# Keypad.net
KiCad netlist of a schematic drawn in Altium Designer
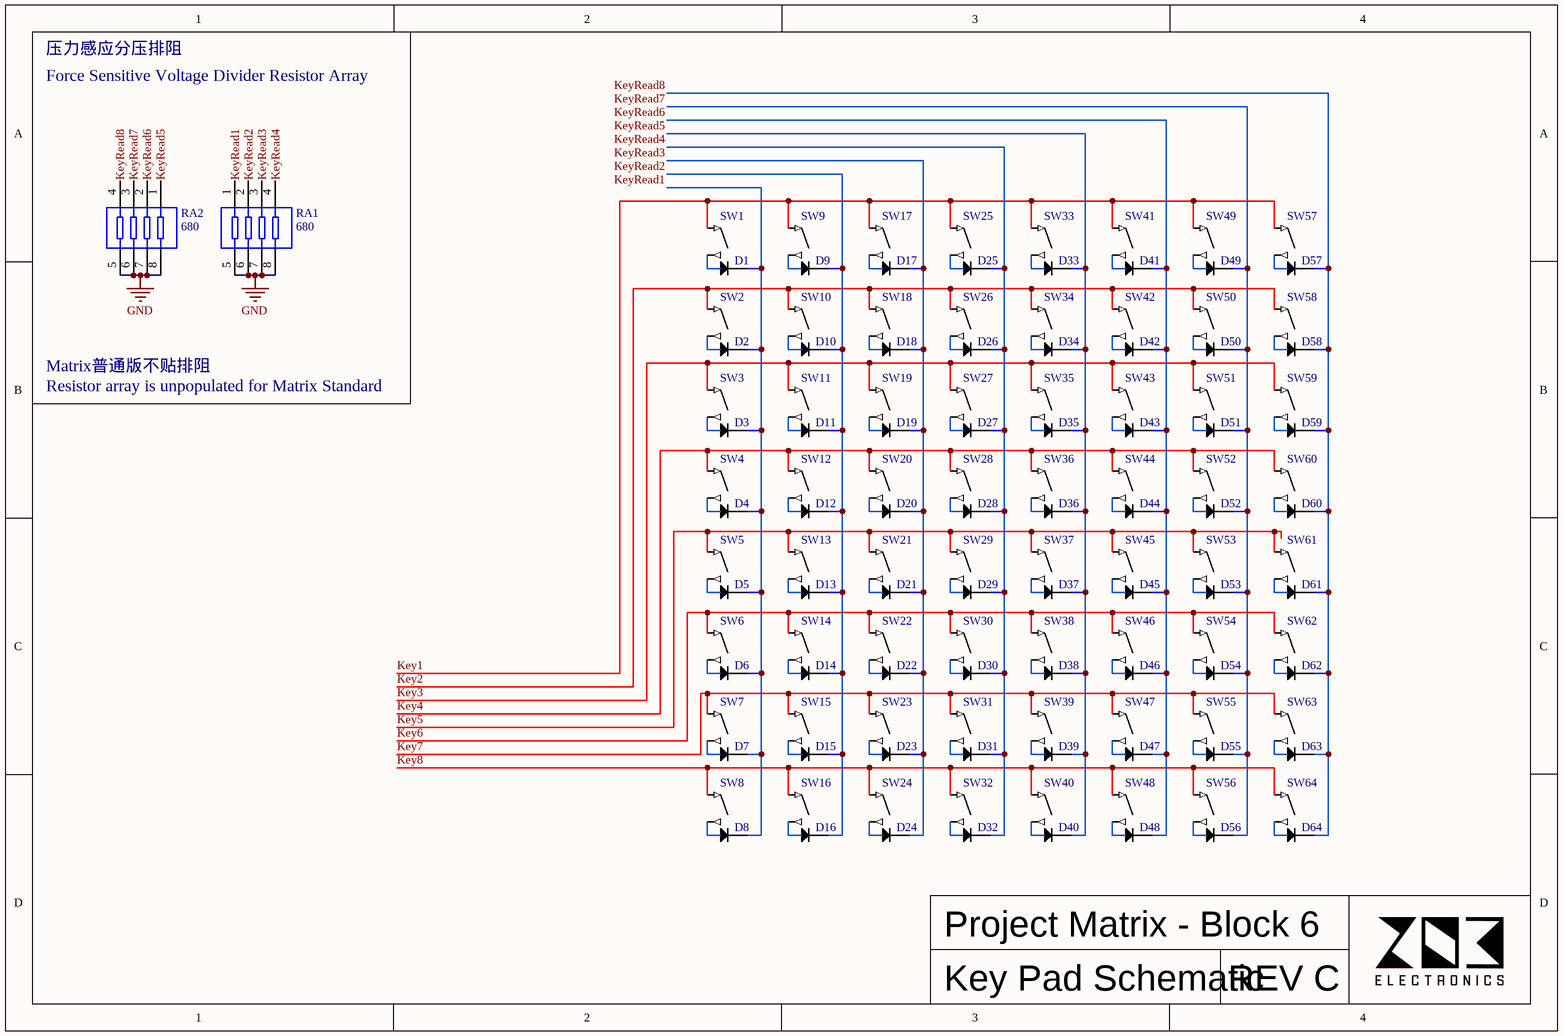
[diagram p0: Keypad.SchDoc]

(export (version "E")
  (design (tool "Eeschema 10.0.6"))
  (components
    (comp (ref "D1") (value "1N4148") (footprint "SOD523") (libsource (lib "Project 64") (part "1N4148")))
    (comp (ref "D2") (value "1N4148") (footprint "SOD523") (libsource (lib "Project 64") (part "1N4148")))
    (comp (ref "D3") (value "1N4148") (footprint "SOD523") (libsource (lib "Project 64") (part "1N4148")))
    (comp (ref "D4") (value "1N4148") (footprint "SOD523") (libsource (lib "Project 64") (part "1N4148")))
    (comp (ref "D5") (value "1N4148") (footprint "SOD523") (libsource (lib "Project 64") (part "1N4148")))
    (comp (ref "D6") (value "1N4148") (footprint "SOD523") (libsource (lib "Project 64") (part "1N4148")))
    (comp (ref "D7") (value "1N4148") (footprint "SOD523") (libsource (lib "Project 64") (part "1N4148")))
    (comp (ref "D8") (value "1N4148") (footprint "SOD523") (libsource (lib "Project 64") (part "1N4148")))
    (comp (ref "D9") (value "1N4148") (footprint "SOD523") (libsource (lib "Project 64") (part "1N4148")))
    (comp (ref "D10") (value "1N4148") (footprint "SOD523") (libsource (lib "Project 64") (part "1N4148")))
    (comp (ref "D11") (value "1N4148") (footprint "SOD523") (libsource (lib "Project 64") (part "1N4148")))
    (comp (ref "D12") (value "1N4148") (footprint "SOD523") (libsource (lib "Project 64") (part "1N4148")))
    (comp (ref "D13") (value "1N4148") (footprint "SOD523") (libsource (lib "Project 64") (part "1N4148")))
    (comp (ref "D14") (value "1N4148") (footprint "SOD523") (libsource (lib "Project 64") (part "1N4148")))
    (comp (ref "D15") (value "1N4148") (footprint "SOD523") (libsource (lib "Project 64") (part "1N4148")))
    (comp (ref "D16") (value "1N4148") (footprint "SOD523") (libsource (lib "Project 64") (part "1N4148")))
    (comp (ref "D17") (value "1N4148") (footprint "SOD523") (libsource (lib "Project 64") (part "1N4148")))
    (comp (ref "D18") (value "1N4148") (footprint "SOD523") (libsource (lib "Project 64") (part "1N4148")))
    (comp (ref "D19") (value "1N4148") (footprint "SOD523") (libsource (lib "Project 64") (part "1N4148")))
    (comp (ref "D20") (value "1N4148") (footprint "SOD523") (libsource (lib "Project 64") (part "1N4148")))
    (comp (ref "D21") (value "1N4148") (footprint "SOD523") (libsource (lib "Project 64") (part "1N4148")))
    (comp (ref "D22") (value "1N4148") (footprint "SOD523") (libsource (lib "Project 64") (part "1N4148")))
    (comp (ref "D23") (value "1N4148") (footprint "SOD523") (libsource (lib "Project 64") (part "1N4148")))
    (comp (ref "D24") (value "1N4148") (footprint "SOD523") (libsource (lib "Project 64") (part "1N4148")))
    (comp (ref "D25") (value "1N4148") (footprint "SOD523") (libsource (lib "Project 64") (part "1N4148")))
    (comp (ref "D26") (value "1N4148") (footprint "SOD523") (libsource (lib "Project 64") (part "1N4148")))
    (comp (ref "D27") (value "1N4148") (footprint "SOD523") (libsource (lib "Project 64") (part "1N4148")))
    (comp (ref "D28") (value "1N4148") (footprint "SOD523") (libsource (lib "Project 64") (part "1N4148")))
    (comp (ref "D29") (value "1N4148") (footprint "SOD523") (libsource (lib "Project 64") (part "1N4148")))
    (comp (ref "D30") (value "1N4148") (footprint "SOD523") (libsource (lib "Project 64") (part "1N4148")))
    (comp (ref "D31") (value "1N4148") (footprint "SOD523") (libsource (lib "Project 64") (part "1N4148")))
    (comp (ref "D32") (value "1N4148") (footprint "SOD523") (libsource (lib "Project 64") (part "1N4148")))
    (comp (ref "D33") (value "1N4148") (footprint "SOD523") (libsource (lib "Project 64") (part "1N4148")))
    (comp (ref "D34") (value "1N4148") (footprint "SOD523") (libsource (lib "Project 64") (part "1N4148")))
    (comp (ref "D35") (value "1N4148") (footprint "SOD523") (libsource (lib "Project 64") (part "1N4148")))
    (comp (ref "D36") (value "1N4148") (footprint "SOD523") (libsource (lib "Project 64") (part "1N4148")))
    (comp (ref "D37") (value "1N4148") (footprint "SOD523") (libsource (lib "Project 64") (part "1N4148")))
    (comp (ref "D38") (value "1N4148") (footprint "SOD523") (libsource (lib "Project 64") (part "1N4148")))
    (comp (ref "D39") (value "1N4148") (footprint "SOD523") (libsource (lib "Project 64") (part "1N4148")))
    (comp (ref "D40") (value "1N4148") (footprint "SOD523") (libsource (lib "Project 64") (part "1N4148")))
    (comp (ref "D41") (value "1N4148") (footprint "SOD523") (libsource (lib "Project 64") (part "1N4148")))
    (comp (ref "D42") (value "1N4148") (footprint "SOD523") (libsource (lib "Project 64") (part "1N4148")))
    (comp (ref "D43") (value "1N4148") (footprint "SOD523") (libsource (lib "Project 64") (part "1N4148")))
    (comp (ref "D44") (value "1N4148") (footprint "SOD523") (libsource (lib "Project 64") (part "1N4148")))
    (comp (ref "D45") (value "1N4148") (footprint "SOD523") (libsource (lib "Project 64") (part "1N4148")))
    (comp (ref "D46") (value "1N4148") (footprint "SOD523") (libsource (lib "Project 64") (part "1N4148")))
    (comp (ref "D47") (value "1N4148") (footprint "SOD523") (libsource (lib "Project 64") (part "1N4148")))
    (comp (ref "D48") (value "1N4148") (footprint "SOD523") (libsource (lib "Project 64") (part "1N4148")))
    (comp (ref "D49") (value "1N4148") (footprint "SOD523") (libsource (lib "Project 64") (part "1N4148")))
    (comp (ref "D50") (value "1N4148") (footprint "SOD523") (libsource (lib "Project 64") (part "1N4148")))
    (comp (ref "D51") (value "1N4148") (footprint "SOD523") (libsource (lib "Project 64") (part "1N4148")))
    (comp (ref "D52") (value "1N4148") (footprint "SOD523") (libsource (lib "Project 64") (part "1N4148")))
    (comp (ref "D53") (value "1N4148") (footprint "SOD523") (libsource (lib "Project 64") (part "1N4148")))
    (comp (ref "D54") (value "1N4148") (footprint "SOD523") (libsource (lib "Project 64") (part "1N4148")))
    (comp (ref "D55") (value "1N4148") (footprint "SOD523") (libsource (lib "Project 64") (part "1N4148")))
    (comp (ref "D56") (value "1N4148") (footprint "SOD523") (libsource (lib "Project 64") (part "1N4148")))
    (comp (ref "D57") (value "1N4148") (footprint "SOD523") (libsource (lib "Project 64") (part "1N4148")))
    (comp (ref "D58") (value "1N4148") (footprint "SOD523") (libsource (lib "Project 64") (part "1N4148")))
    (comp (ref "D59") (value "1N4148") (footprint "SOD523") (libsource (lib "Project 64") (part "1N4148")))
    (comp (ref "D60") (value "1N4148") (footprint "SOD523") (libsource (lib "Project 64") (part "1N4148")))
    (comp (ref "D61") (value "1N4148") (footprint "SOD523") (libsource (lib "Project 64") (part "1N4148")))
    (comp (ref "D62") (value "1N4148") (footprint "SOD523") (libsource (lib "Project 64") (part "1N4148")))
    (comp (ref "D63") (value "1N4148") (footprint "SOD523") (libsource (lib "Project 64") (part "1N4148")))
    (comp (ref "D64") (value "1N4148") (footprint "SOD523") (libsource (lib "Project 64") (part "1N4148")))
    (comp (ref "RA1")
      (value "680")
      (footprint "8P4R")
      (description "Touch Bar")
      (libsource (lib "") (part "4R8P Resistor_1"))
    )
    (comp (ref "RA2")
      (value "680")
      (footprint "8P4R")
      (description "Touch Bar")
      (libsource (lib "203") (part "4R8P Resistor"))
    )
    (comp (ref "SW1") (value "~") (footprint "FSR Pad") (libsource (lib "Project 64") (part "SW")))
    (comp (ref "SW2") (value "~") (footprint "FSR Pad") (libsource (lib "Project 64") (part "SW")))
    (comp (ref "SW3") (value "~") (footprint "FSR Pad") (libsource (lib "Project 64") (part "SW")))
    (comp (ref "SW4") (value "~") (footprint "FSR Pad") (libsource (lib "Project 64") (part "SW")))
    (comp (ref "SW5") (value "~") (footprint "FSR Pad") (libsource (lib "Project 64") (part "SW")))
    (comp (ref "SW6") (value "~") (footprint "FSR Pad") (libsource (lib "Project 64") (part "SW")))
    (comp (ref "SW7") (value "~") (footprint "FSR Pad") (libsource (lib "Project 64") (part "SW")))
    (comp (ref "SW8") (value "~") (footprint "FSR Pad") (libsource (lib "Project 64") (part "SW")))
    (comp (ref "SW9") (value "~") (footprint "FSR Pad") (libsource (lib "Project 64") (part "SW")))
    (comp (ref "SW10") (value "~") (footprint "FSR Pad") (libsource (lib "Project 64") (part "SW")))
    (comp (ref "SW11") (value "~") (footprint "FSR Pad") (libsource (lib "Project 64") (part "SW")))
    (comp (ref "SW12") (value "~") (footprint "FSR Pad") (libsource (lib "Project 64") (part "SW")))
    (comp (ref "SW13") (value "~") (footprint "FSR Pad") (libsource (lib "Project 64") (part "SW")))
    (comp (ref "SW14") (value "~") (footprint "FSR Pad") (libsource (lib "Project 64") (part "SW")))
    (comp (ref "SW15") (value "~") (footprint "FSR Pad") (libsource (lib "Project 64") (part "SW")))
    (comp (ref "SW16") (value "~") (footprint "FSR Pad") (libsource (lib "Project 64") (part "SW")))
    (comp (ref "SW17") (value "~") (footprint "FSR Pad") (libsource (lib "Project 64") (part "SW")))
    (comp (ref "SW18") (value "~") (footprint "FSR Pad") (libsource (lib "Project 64") (part "SW")))
    (comp (ref "SW19") (value "~") (footprint "FSR Pad") (libsource (lib "Project 64") (part "SW")))
    (comp (ref "SW20") (value "~") (footprint "FSR Pad") (libsource (lib "Project 64") (part "SW")))
    (comp (ref "SW21") (value "~") (footprint "FSR Pad") (libsource (lib "Project 64") (part "SW")))
    (comp (ref "SW22") (value "~") (footprint "FSR Pad") (libsource (lib "Project 64") (part "SW")))
    (comp (ref "SW23") (value "~") (footprint "FSR Pad") (libsource (lib "Project 64") (part "SW")))
    (comp (ref "SW24") (value "~") (footprint "FSR Pad") (libsource (lib "Project 64") (part "SW")))
    (comp (ref "SW25") (value "~") (footprint "FSR Pad") (libsource (lib "Project 64") (part "SW")))
    (comp (ref "SW26") (value "~") (footprint "FSR Pad") (libsource (lib "Project 64") (part "SW")))
    (comp (ref "SW27") (value "~") (footprint "FSR Pad") (libsource (lib "Project 64") (part "SW")))
    (comp (ref "SW28") (value "~") (footprint "FSR Pad") (libsource (lib "Project 64") (part "SW")))
    (comp (ref "SW29") (value "~") (footprint "FSR Pad") (libsource (lib "Project 64") (part "SW")))
    (comp (ref "SW30") (value "~") (footprint "FSR Pad") (libsource (lib "Project 64") (part "SW")))
    (comp (ref "SW31") (value "~") (footprint "FSR Pad") (libsource (lib "Project 64") (part "SW")))
    (comp (ref "SW32") (value "~") (footprint "FSR Pad") (libsource (lib "Project 64") (part "SW")))
    (comp (ref "SW33") (value "~") (footprint "FSR Pad") (libsource (lib "Project 64") (part "SW")))
    (comp (ref "SW34") (value "~") (footprint "FSR Pad") (libsource (lib "Project 64") (part "SW")))
    (comp (ref "SW35") (value "~") (footprint "FSR Pad") (libsource (lib "Project 64") (part "SW")))
    (comp (ref "SW36") (value "~") (footprint "FSR Pad") (libsource (lib "Project 64") (part "SW")))
    (comp (ref "SW37") (value "~") (footprint "FSR Pad") (libsource (lib "Project 64") (part "SW")))
    (comp (ref "SW38") (value "~") (footprint "FSR Pad") (libsource (lib "Project 64") (part "SW")))
    (comp (ref "SW39") (value "~") (footprint "FSR Pad") (libsource (lib "Project 64") (part "SW")))
    (comp (ref "SW40") (value "~") (footprint "FSR Pad") (libsource (lib "Project 64") (part "SW")))
    (comp (ref "SW41") (value "~") (footprint "FSR Pad") (libsource (lib "Project 64") (part "SW")))
    (comp (ref "SW42") (value "~") (footprint "FSR Pad") (libsource (lib "Project 64") (part "SW")))
    (comp (ref "SW43") (value "~") (footprint "FSR Pad") (libsource (lib "Project 64") (part "SW")))
    (comp (ref "SW44") (value "~") (footprint "FSR Pad") (libsource (lib "Project 64") (part "SW")))
    (comp (ref "SW45") (value "~") (footprint "FSR Pad") (libsource (lib "Project 64") (part "SW")))
    (comp (ref "SW46") (value "~") (footprint "FSR Pad") (libsource (lib "Project 64") (part "SW")))
    (comp (ref "SW47") (value "~") (footprint "FSR Pad") (libsource (lib "Project 64") (part "SW")))
    (comp (ref "SW48") (value "~") (footprint "FSR Pad") (libsource (lib "Project 64") (part "SW")))
    (comp (ref "SW49") (value "~") (footprint "FSR Pad") (libsource (lib "Project 64") (part "SW")))
    (comp (ref "SW50") (value "~") (footprint "FSR Pad") (libsource (lib "Project 64") (part "SW")))
    (comp (ref "SW51") (value "~") (footprint "FSR Pad") (libsource (lib "Project 64") (part "SW")))
    (comp (ref "SW52") (value "~") (footprint "FSR Pad") (libsource (lib "Project 64") (part "SW")))
    (comp (ref "SW53") (value "~") (footprint "FSR Pad") (libsource (lib "Project 64") (part "SW")))
    (comp (ref "SW54") (value "~") (footprint "FSR Pad") (libsource (lib "Project 64") (part "SW")))
    (comp (ref "SW55") (value "~") (footprint "FSR Pad") (libsource (lib "Project 64") (part "SW")))
    (comp (ref "SW56") (value "~") (footprint "FSR Pad") (libsource (lib "Project 64") (part "SW")))
    (comp (ref "SW57") (value "~") (footprint "FSR Pad") (libsource (lib "Project 64") (part "SW")))
    (comp (ref "SW58") (value "~") (footprint "FSR Pad") (libsource (lib "Project 64") (part "SW")))
    (comp (ref "SW59") (value "~") (footprint "FSR Pad") (libsource (lib "Project 64") (part "SW")))
    (comp (ref "SW60") (value "~") (footprint "FSR Pad") (libsource (lib "Project 64") (part "SW")))
    (comp (ref "SW61") (value "~") (footprint "FSR Pad") (libsource (lib "Project 64") (part "SW")))
    (comp (ref "SW62") (value "~") (footprint "FSR Pad") (libsource (lib "Project 64") (part "SW")))
    (comp (ref "SW63") (value "~") (footprint "FSR Pad") (libsource (lib "Project 64") (part "SW")))
    (comp (ref "SW64") (value "~") (footprint "FSR Pad") (libsource (lib "Project 64") (part "SW")))
  )
  (nets
    (net (code "1") (name "/Key1") (class "Default")
      (node (ref "SW1") (pin "1") (pinfunction "1_1") (pintype "input"))
      (node (ref "SW17") (pin "1") (pinfunction "1_1") (pintype "input"))
      (node (ref "SW25") (pin "1") (pinfunction "1_1") (pintype "input"))
      (node (ref "SW33") (pin "1") (pinfunction "1_1") (pintype "input"))
      (node (ref "SW41") (pin "1") (pinfunction "1_1") (pintype "input"))
      (node (ref "SW49") (pin "1") (pinfunction "1_1") (pintype "input"))
      (node (ref "SW57") (pin "1") (pinfunction "1_1") (pintype "input"))
      (node (ref "SW9") (pin "1") (pinfunction "1_1") (pintype "input"))
    )
    (net (code "2") (name "/Key2") (class "Default")
      (node (ref "SW10") (pin "1") (pinfunction "1_1") (pintype "input"))
      (node (ref "SW18") (pin "1") (pinfunction "1_1") (pintype "input"))
      (node (ref "SW2") (pin "1") (pinfunction "1_1") (pintype "input"))
      (node (ref "SW26") (pin "1") (pinfunction "1_1") (pintype "input"))
      (node (ref "SW34") (pin "1") (pinfunction "1_1") (pintype "input"))
      (node (ref "SW42") (pin "1") (pinfunction "1_1") (pintype "input"))
      (node (ref "SW50") (pin "1") (pinfunction "1_1") (pintype "input"))
      (node (ref "SW58") (pin "1") (pinfunction "1_1") (pintype "input"))
    )
    (net (code "3") (name "/Key3") (class "Default")
      (node (ref "SW11") (pin "1") (pinfunction "1_1") (pintype "input"))
      (node (ref "SW19") (pin "1") (pinfunction "1_1") (pintype "input"))
      (node (ref "SW27") (pin "1") (pinfunction "1_1") (pintype "input"))
      (node (ref "SW3") (pin "1") (pinfunction "1_1") (pintype "input"))
      (node (ref "SW35") (pin "1") (pinfunction "1_1") (pintype "input"))
      (node (ref "SW43") (pin "1") (pinfunction "1_1") (pintype "input"))
      (node (ref "SW51") (pin "1") (pinfunction "1_1") (pintype "input"))
      (node (ref "SW59") (pin "1") (pinfunction "1_1") (pintype "input"))
    )
    (net (code "4") (name "/Key4") (class "Default")
      (node (ref "SW12") (pin "1") (pinfunction "1_1") (pintype "input"))
      (node (ref "SW20") (pin "1") (pinfunction "1_1") (pintype "input"))
      (node (ref "SW28") (pin "1") (pinfunction "1_1") (pintype "input"))
      (node (ref "SW36") (pin "1") (pinfunction "1_1") (pintype "input"))
      (node (ref "SW4") (pin "1") (pinfunction "1_1") (pintype "input"))
      (node (ref "SW44") (pin "1") (pinfunction "1_1") (pintype "input"))
      (node (ref "SW52") (pin "1") (pinfunction "1_1") (pintype "input"))
      (node (ref "SW60") (pin "1") (pinfunction "1_1") (pintype "input"))
    )
    (net (code "5") (name "/Key5") (class "Default")
      (node (ref "SW13") (pin "1") (pinfunction "1_1") (pintype "input"))
      (node (ref "SW21") (pin "1") (pinfunction "1_1") (pintype "input"))
      (node (ref "SW29") (pin "1") (pinfunction "1_1") (pintype "input"))
      (node (ref "SW37") (pin "1") (pinfunction "1_1") (pintype "input"))
      (node (ref "SW45") (pin "1") (pinfunction "1_1") (pintype "input"))
      (node (ref "SW5") (pin "1") (pinfunction "1_1") (pintype "input"))
      (node (ref "SW53") (pin "1") (pinfunction "1_1") (pintype "input"))
      (node (ref "SW61") (pin "1") (pinfunction "1_1") (pintype "input"))
    )
    (net (code "6") (name "/Key6") (class "Default")
      (node (ref "SW14") (pin "1") (pinfunction "1_1") (pintype "input"))
      (node (ref "SW22") (pin "1") (pinfunction "1_1") (pintype "input"))
      (node (ref "SW30") (pin "1") (pinfunction "1_1") (pintype "input"))
      (node (ref "SW38") (pin "1") (pinfunction "1_1") (pintype "input"))
      (node (ref "SW46") (pin "1") (pinfunction "1_1") (pintype "input"))
      (node (ref "SW54") (pin "1") (pinfunction "1_1") (pintype "input"))
      (node (ref "SW6") (pin "1") (pinfunction "1_1") (pintype "input"))
      (node (ref "SW62") (pin "1") (pinfunction "1_1") (pintype "input"))
    )
    (net (code "7") (name "/Key7") (class "Default")
      (node (ref "SW15") (pin "1") (pinfunction "1_1") (pintype "input"))
      (node (ref "SW23") (pin "1") (pinfunction "1_1") (pintype "input"))
      (node (ref "SW31") (pin "1") (pinfunction "1_1") (pintype "input"))
      (node (ref "SW39") (pin "1") (pinfunction "1_1") (pintype "input"))
      (node (ref "SW47") (pin "1") (pinfunction "1_1") (pintype "input"))
      (node (ref "SW55") (pin "1") (pinfunction "1_1") (pintype "input"))
      (node (ref "SW63") (pin "1") (pinfunction "1_1") (pintype "input"))
      (node (ref "SW7") (pin "1") (pinfunction "1_1") (pintype "input"))
    )
    (net (code "8") (name "/Key8") (class "Default")
      (node (ref "SW16") (pin "1") (pinfunction "1_1") (pintype "input"))
      (node (ref "SW24") (pin "1") (pinfunction "1_1") (pintype "input"))
      (node (ref "SW32") (pin "1") (pinfunction "1_1") (pintype "input"))
      (node (ref "SW40") (pin "1") (pinfunction "1_1") (pintype "input"))
      (node (ref "SW48") (pin "1") (pinfunction "1_1") (pintype "input"))
      (node (ref "SW56") (pin "1") (pinfunction "1_1") (pintype "input"))
      (node (ref "SW64") (pin "1") (pinfunction "1_1") (pintype "input"))
      (node (ref "SW8") (pin "1") (pinfunction "1_1") (pintype "input"))
    )
    (net (code "9") (name "/KeyRead1") (class "Default")
      (node (ref "D1") (pin "2") (pinfunction "2_2") (pintype "passive"))
      (node (ref "D2") (pin "2") (pinfunction "2_2") (pintype "passive"))
      (node (ref "D3") (pin "2") (pinfunction "2_2") (pintype "passive"))
      (node (ref "D4") (pin "2") (pinfunction "2_2") (pintype "passive"))
      (node (ref "D5") (pin "2") (pinfunction "2_2") (pintype "passive"))
      (node (ref "D6") (pin "2") (pinfunction "2_2") (pintype "passive"))
      (node (ref "D7") (pin "2") (pinfunction "2_2") (pintype "passive"))
      (node (ref "D8") (pin "2") (pinfunction "2_2") (pintype "passive"))
      (node (ref "RA1") (pin "1") (pinfunction "1_1") (pintype "passive"))
    )
    (net (code "10") (name "/KeyRead2") (class "Default")
      (node (ref "D10") (pin "2") (pinfunction "2_2") (pintype "passive"))
      (node (ref "D11") (pin "2") (pinfunction "2_2") (pintype "passive"))
      (node (ref "D12") (pin "2") (pinfunction "2_2") (pintype "passive"))
      (node (ref "D13") (pin "2") (pinfunction "2_2") (pintype "passive"))
      (node (ref "D14") (pin "2") (pinfunction "2_2") (pintype "passive"))
      (node (ref "D15") (pin "2") (pinfunction "2_2") (pintype "passive"))
      (node (ref "D16") (pin "2") (pinfunction "2_2") (pintype "passive"))
      (node (ref "D9") (pin "2") (pinfunction "2_2") (pintype "passive"))
      (node (ref "RA1") (pin "2") (pinfunction "2_2") (pintype "passive"))
    )
    (net (code "11") (name "/KeyRead3") (class "Default")
      (node (ref "D17") (pin "2") (pinfunction "2_2") (pintype "passive"))
      (node (ref "D18") (pin "2") (pinfunction "2_2") (pintype "passive"))
      (node (ref "D19") (pin "2") (pinfunction "2_2") (pintype "passive"))
      (node (ref "D20") (pin "2") (pinfunction "2_2") (pintype "passive"))
      (node (ref "D21") (pin "2") (pinfunction "2_2") (pintype "passive"))
      (node (ref "D22") (pin "2") (pinfunction "2_2") (pintype "passive"))
      (node (ref "D23") (pin "2") (pinfunction "2_2") (pintype "passive"))
      (node (ref "D24") (pin "2") (pinfunction "2_2") (pintype "passive"))
      (node (ref "RA1") (pin "3") (pinfunction "3_3") (pintype "passive"))
    )
    (net (code "12") (name "/KeyRead4") (class "Default")
      (node (ref "D25") (pin "2") (pinfunction "2_2") (pintype "passive"))
      (node (ref "D26") (pin "2") (pinfunction "2_2") (pintype "passive"))
      (node (ref "D27") (pin "2") (pinfunction "2_2") (pintype "passive"))
      (node (ref "D28") (pin "2") (pinfunction "2_2") (pintype "passive"))
      (node (ref "D29") (pin "2") (pinfunction "2_2") (pintype "passive"))
      (node (ref "D30") (pin "2") (pinfunction "2_2") (pintype "passive"))
      (node (ref "D31") (pin "2") (pinfunction "2_2") (pintype "passive"))
      (node (ref "D32") (pin "2") (pinfunction "2_2") (pintype "passive"))
      (node (ref "RA1") (pin "4") (pinfunction "4_4") (pintype "passive"))
    )
    (net (code "13") (name "/KeyRead5") (class "Default")
      (node (ref "D33") (pin "2") (pinfunction "2_2") (pintype "passive"))
      (node (ref "D34") (pin "2") (pinfunction "2_2") (pintype "passive"))
      (node (ref "D35") (pin "2") (pinfunction "2_2") (pintype "passive"))
      (node (ref "D36") (pin "2") (pinfunction "2_2") (pintype "passive"))
      (node (ref "D37") (pin "2") (pinfunction "2_2") (pintype "passive"))
      (node (ref "D38") (pin "2") (pinfunction "2_2") (pintype "passive"))
      (node (ref "D39") (pin "2") (pinfunction "2_2") (pintype "passive"))
      (node (ref "D40") (pin "2") (pinfunction "2_2") (pintype "passive"))
      (node (ref "RA2") (pin "1") (pinfunction "1_1") (pintype "passive"))
    )
    (net (code "14") (name "/KeyRead6") (class "Default")
      (node (ref "D41") (pin "2") (pinfunction "2_2") (pintype "passive"))
      (node (ref "D42") (pin "2") (pinfunction "2_2") (pintype "passive"))
      (node (ref "D43") (pin "2") (pinfunction "2_2") (pintype "passive"))
      (node (ref "D44") (pin "2") (pinfunction "2_2") (pintype "passive"))
      (node (ref "D45") (pin "2") (pinfunction "2_2") (pintype "passive"))
      (node (ref "D46") (pin "2") (pinfunction "2_2") (pintype "passive"))
      (node (ref "D47") (pin "2") (pinfunction "2_2") (pintype "passive"))
      (node (ref "D48") (pin "2") (pinfunction "2_2") (pintype "passive"))
      (node (ref "RA2") (pin "2") (pinfunction "2_2") (pintype "passive"))
    )
    (net (code "15") (name "/KeyRead7") (class "Default")
      (node (ref "D49") (pin "2") (pinfunction "2_2") (pintype "passive"))
      (node (ref "D50") (pin "2") (pinfunction "2_2") (pintype "passive"))
      (node (ref "D51") (pin "2") (pinfunction "2_2") (pintype "passive"))
      (node (ref "D52") (pin "2") (pinfunction "2_2") (pintype "passive"))
      (node (ref "D53") (pin "2") (pinfunction "2_2") (pintype "passive"))
      (node (ref "D54") (pin "2") (pinfunction "2_2") (pintype "passive"))
      (node (ref "D55") (pin "2") (pinfunction "2_2") (pintype "passive"))
      (node (ref "D56") (pin "2") (pinfunction "2_2") (pintype "passive"))
      (node (ref "RA2") (pin "3") (pinfunction "3_3") (pintype "passive"))
    )
    (net (code "16") (name "/KeyRead8") (class "Default")
      (node (ref "D57") (pin "2") (pinfunction "2_2") (pintype "passive"))
      (node (ref "D58") (pin "2") (pinfunction "2_2") (pintype "passive"))
      (node (ref "D59") (pin "2") (pinfunction "2_2") (pintype "passive"))
      (node (ref "D60") (pin "2") (pinfunction "2_2") (pintype "passive"))
      (node (ref "D61") (pin "2") (pinfunction "2_2") (pintype "passive"))
      (node (ref "D62") (pin "2") (pinfunction "2_2") (pintype "passive"))
      (node (ref "D63") (pin "2") (pinfunction "2_2") (pintype "passive"))
      (node (ref "D64") (pin "2") (pinfunction "2_2") (pintype "passive"))
      (node (ref "RA2") (pin "4") (pinfunction "4_4") (pintype "passive"))
    )
    (net (code "17") (name "GND") (class "Default")
      (node (ref "RA1") (pin "5") (pinfunction "5_5") (pintype "passive"))
      (node (ref "RA1") (pin "6") (pinfunction "6_6") (pintype "passive"))
      (node (ref "RA1") (pin "7") (pinfunction "7_7") (pintype "passive"))
      (node (ref "RA1") (pin "8") (pinfunction "8_8") (pintype "passive"))
      (node (ref "RA2") (pin "5") (pinfunction "5_5") (pintype "passive"))
      (node (ref "RA2") (pin "6") (pinfunction "6_6") (pintype "passive"))
      (node (ref "RA2") (pin "7") (pinfunction "7_7") (pintype "passive"))
      (node (ref "RA2") (pin "8") (pinfunction "8_8") (pintype "passive"))
    )
    (net (code "18") (name "Net-(SW1-Out)") (class "Default")
      (node (ref "D1") (pin "1") (pinfunction "1_1") (pintype "passive"))
      (node (ref "SW1") (pin "2") (pinfunction "Out_2") (pintype "output"))
    )
    (net (code "19") (name "Net-(SW2-Out)") (class "Default")
      (node (ref "D2") (pin "1") (pinfunction "1_1") (pintype "passive"))
      (node (ref "SW2") (pin "2") (pinfunction "Out_2") (pintype "output"))
    )
    (net (code "20") (name "Net-(SW3-Out)") (class "Default")
      (node (ref "D3") (pin "1") (pinfunction "1_1") (pintype "passive"))
      (node (ref "SW3") (pin "2") (pinfunction "Out_2") (pintype "output"))
    )
    (net (code "21") (name "Net-(SW4-Out)") (class "Default")
      (node (ref "D4") (pin "1") (pinfunction "1_1") (pintype "passive"))
      (node (ref "SW4") (pin "2") (pinfunction "Out_2") (pintype "output"))
    )
    (net (code "22") (name "Net-(SW5-Out)") (class "Default")
      (node (ref "D5") (pin "1") (pinfunction "1_1") (pintype "passive"))
      (node (ref "SW5") (pin "2") (pinfunction "Out_2") (pintype "output"))
    )
    (net (code "23") (name "Net-(SW6-Out)") (class "Default")
      (node (ref "D6") (pin "1") (pinfunction "1_1") (pintype "passive"))
      (node (ref "SW6") (pin "2") (pinfunction "Out_2") (pintype "output"))
    )
    (net (code "24") (name "Net-(SW7-Out)") (class "Default")
      (node (ref "D7") (pin "1") (pinfunction "1_1") (pintype "passive"))
      (node (ref "SW7") (pin "2") (pinfunction "Out_2") (pintype "output"))
    )
    (net (code "25") (name "Net-(SW8-Out)") (class "Default")
      (node (ref "D8") (pin "1") (pinfunction "1_1") (pintype "passive"))
      (node (ref "SW8") (pin "2") (pinfunction "Out_2") (pintype "output"))
    )
    (net (code "26") (name "Net-(SW9-Out)") (class "Default")
      (node (ref "D9") (pin "1") (pinfunction "1_1") (pintype "passive"))
      (node (ref "SW9") (pin "2") (pinfunction "Out_2") (pintype "output"))
    )
    (net (code "27") (name "Net-(SW10-Out)") (class "Default")
      (node (ref "D10") (pin "1") (pinfunction "1_1") (pintype "passive"))
      (node (ref "SW10") (pin "2") (pinfunction "Out_2") (pintype "output"))
    )
    (net (code "28") (name "Net-(SW11-Out)") (class "Default")
      (node (ref "D11") (pin "1") (pinfunction "1_1") (pintype "passive"))
      (node (ref "SW11") (pin "2") (pinfunction "Out_2") (pintype "output"))
    )
    (net (code "29") (name "Net-(SW12-Out)") (class "Default")
      (node (ref "D12") (pin "1") (pinfunction "1_1") (pintype "passive"))
      (node (ref "SW12") (pin "2") (pinfunction "Out_2") (pintype "output"))
    )
    (net (code "30") (name "Net-(SW13-Out)") (class "Default")
      (node (ref "D13") (pin "1") (pinfunction "1_1") (pintype "passive"))
      (node (ref "SW13") (pin "2") (pinfunction "Out_2") (pintype "output"))
    )
    (net (code "31") (name "Net-(SW14-Out)") (class "Default")
      (node (ref "D14") (pin "1") (pinfunction "1_1") (pintype "passive"))
      (node (ref "SW14") (pin "2") (pinfunction "Out_2") (pintype "output"))
    )
    (net (code "32") (name "Net-(SW15-Out)") (class "Default")
      (node (ref "D15") (pin "1") (pinfunction "1_1") (pintype "passive"))
      (node (ref "SW15") (pin "2") (pinfunction "Out_2") (pintype "output"))
    )
    (net (code "33") (name "Net-(SW16-Out)") (class "Default")
      (node (ref "D16") (pin "1") (pinfunction "1_1") (pintype "passive"))
      (node (ref "SW16") (pin "2") (pinfunction "Out_2") (pintype "output"))
    )
    (net (code "34") (name "Net-(SW17-Out)") (class "Default")
      (node (ref "D17") (pin "1") (pinfunction "1_1") (pintype "passive"))
      (node (ref "SW17") (pin "2") (pinfunction "Out_2") (pintype "output"))
    )
    (net (code "35") (name "Net-(SW18-Out)") (class "Default")
      (node (ref "D18") (pin "1") (pinfunction "1_1") (pintype "passive"))
      (node (ref "SW18") (pin "2") (pinfunction "Out_2") (pintype "output"))
    )
    (net (code "36") (name "Net-(SW19-Out)") (class "Default")
      (node (ref "D19") (pin "1") (pinfunction "1_1") (pintype "passive"))
      (node (ref "SW19") (pin "2") (pinfunction "Out_2") (pintype "output"))
    )
    (net (code "37") (name "Net-(SW20-Out)") (class "Default")
      (node (ref "D20") (pin "1") (pinfunction "1_1") (pintype "passive"))
      (node (ref "SW20") (pin "2") (pinfunction "Out_2") (pintype "output"))
    )
    (net (code "38") (name "Net-(SW21-Out)") (class "Default")
      (node (ref "D21") (pin "1") (pinfunction "1_1") (pintype "passive"))
      (node (ref "SW21") (pin "2") (pinfunction "Out_2") (pintype "output"))
    )
    (net (code "39") (name "Net-(SW22-Out)") (class "Default")
      (node (ref "D22") (pin "1") (pinfunction "1_1") (pintype "passive"))
      (node (ref "SW22") (pin "2") (pinfunction "Out_2") (pintype "output"))
    )
    (net (code "40") (name "Net-(SW23-Out)") (class "Default")
      (node (ref "D23") (pin "1") (pinfunction "1_1") (pintype "passive"))
      (node (ref "SW23") (pin "2") (pinfunction "Out_2") (pintype "output"))
    )
    (net (code "41") (name "Net-(SW24-Out)") (class "Default")
      (node (ref "D24") (pin "1") (pinfunction "1_1") (pintype "passive"))
      (node (ref "SW24") (pin "2") (pinfunction "Out_2") (pintype "output"))
    )
    (net (code "42") (name "Net-(SW25-Out)") (class "Default")
      (node (ref "D25") (pin "1") (pinfunction "1_1") (pintype "passive"))
      (node (ref "SW25") (pin "2") (pinfunction "Out_2") (pintype "output"))
    )
    (net (code "43") (name "Net-(SW26-Out)") (class "Default")
      (node (ref "D26") (pin "1") (pinfunction "1_1") (pintype "passive"))
      (node (ref "SW26") (pin "2") (pinfunction "Out_2") (pintype "output"))
    )
    (net (code "44") (name "Net-(SW27-Out)") (class "Default")
      (node (ref "D27") (pin "1") (pinfunction "1_1") (pintype "passive"))
      (node (ref "SW27") (pin "2") (pinfunction "Out_2") (pintype "output"))
    )
    (net (code "45") (name "Net-(SW28-Out)") (class "Default")
      (node (ref "D28") (pin "1") (pinfunction "1_1") (pintype "passive"))
      (node (ref "SW28") (pin "2") (pinfunction "Out_2") (pintype "output"))
    )
    (net (code "46") (name "Net-(SW29-Out)") (class "Default")
      (node (ref "D29") (pin "1") (pinfunction "1_1") (pintype "passive"))
      (node (ref "SW29") (pin "2") (pinfunction "Out_2") (pintype "output"))
    )
    (net (code "47") (name "Net-(SW30-Out)") (class "Default")
      (node (ref "D30") (pin "1") (pinfunction "1_1") (pintype "passive"))
      (node (ref "SW30") (pin "2") (pinfunction "Out_2") (pintype "output"))
    )
    (net (code "48") (name "Net-(SW31-Out)") (class "Default")
      (node (ref "D31") (pin "1") (pinfunction "1_1") (pintype "passive"))
      (node (ref "SW31") (pin "2") (pinfunction "Out_2") (pintype "output"))
    )
    (net (code "49") (name "Net-(SW32-Out)") (class "Default")
      (node (ref "D32") (pin "1") (pinfunction "1_1") (pintype "passive"))
      (node (ref "SW32") (pin "2") (pinfunction "Out_2") (pintype "output"))
    )
    (net (code "50") (name "Net-(SW33-Out)") (class "Default")
      (node (ref "D33") (pin "1") (pinfunction "1_1") (pintype "passive"))
      (node (ref "SW33") (pin "2") (pinfunction "Out_2") (pintype "output"))
    )
    (net (code "51") (name "Net-(SW34-Out)") (class "Default")
      (node (ref "D34") (pin "1") (pinfunction "1_1") (pintype "passive"))
      (node (ref "SW34") (pin "2") (pinfunction "Out_2") (pintype "output"))
    )
    (net (code "52") (name "Net-(SW35-Out)") (class "Default")
      (node (ref "D35") (pin "1") (pinfunction "1_1") (pintype "passive"))
      (node (ref "SW35") (pin "2") (pinfunction "Out_2") (pintype "output"))
    )
    (net (code "53") (name "Net-(SW36-Out)") (class "Default")
      (node (ref "D36") (pin "1") (pinfunction "1_1") (pintype "passive"))
      (node (ref "SW36") (pin "2") (pinfunction "Out_2") (pintype "output"))
    )
    (net (code "54") (name "Net-(SW37-Out)") (class "Default")
      (node (ref "D37") (pin "1") (pinfunction "1_1") (pintype "passive"))
      (node (ref "SW37") (pin "2") (pinfunction "Out_2") (pintype "output"))
    )
    (net (code "55") (name "Net-(SW38-Out)") (class "Default")
      (node (ref "D38") (pin "1") (pinfunction "1_1") (pintype "passive"))
      (node (ref "SW38") (pin "2") (pinfunction "Out_2") (pintype "output"))
    )
    (net (code "56") (name "Net-(SW39-Out)") (class "Default")
      (node (ref "D39") (pin "1") (pinfunction "1_1") (pintype "passive"))
      (node (ref "SW39") (pin "2") (pinfunction "Out_2") (pintype "output"))
    )
    (net (code "57") (name "Net-(SW40-Out)") (class "Default")
      (node (ref "D40") (pin "1") (pinfunction "1_1") (pintype "passive"))
      (node (ref "SW40") (pin "2") (pinfunction "Out_2") (pintype "output"))
    )
    (net (code "58") (name "Net-(SW41-Out)") (class "Default")
      (node (ref "D41") (pin "1") (pinfunction "1_1") (pintype "passive"))
      (node (ref "SW41") (pin "2") (pinfunction "Out_2") (pintype "output"))
    )
    (net (code "59") (name "Net-(SW42-Out)") (class "Default")
      (node (ref "D42") (pin "1") (pinfunction "1_1") (pintype "passive"))
      (node (ref "SW42") (pin "2") (pinfunction "Out_2") (pintype "output"))
    )
    (net (code "60") (name "Net-(SW43-Out)") (class "Default")
      (node (ref "D43") (pin "1") (pinfunction "1_1") (pintype "passive"))
      (node (ref "SW43") (pin "2") (pinfunction "Out_2") (pintype "output"))
    )
    (net (code "61") (name "Net-(SW44-Out)") (class "Default")
      (node (ref "D44") (pin "1") (pinfunction "1_1") (pintype "passive"))
      (node (ref "SW44") (pin "2") (pinfunction "Out_2") (pintype "output"))
    )
    (net (code "62") (name "Net-(SW45-Out)") (class "Default")
      (node (ref "D45") (pin "1") (pinfunction "1_1") (pintype "passive"))
      (node (ref "SW45") (pin "2") (pinfunction "Out_2") (pintype "output"))
    )
    (net (code "63") (name "Net-(SW46-Out)") (class "Default")
      (node (ref "D46") (pin "1") (pinfunction "1_1") (pintype "passive"))
      (node (ref "SW46") (pin "2") (pinfunction "Out_2") (pintype "output"))
    )
    (net (code "64") (name "Net-(SW47-Out)") (class "Default")
      (node (ref "D47") (pin "1") (pinfunction "1_1") (pintype "passive"))
      (node (ref "SW47") (pin "2") (pinfunction "Out_2") (pintype "output"))
    )
    (net (code "65") (name "Net-(SW48-Out)") (class "Default")
      (node (ref "D48") (pin "1") (pinfunction "1_1") (pintype "passive"))
      (node (ref "SW48") (pin "2") (pinfunction "Out_2") (pintype "output"))
    )
    (net (code "66") (name "Net-(SW49-Out)") (class "Default")
      (node (ref "D49") (pin "1") (pinfunction "1_1") (pintype "passive"))
      (node (ref "SW49") (pin "2") (pinfunction "Out_2") (pintype "output"))
    )
    (net (code "67") (name "Net-(SW50-Out)") (class "Default")
      (node (ref "D50") (pin "1") (pinfunction "1_1") (pintype "passive"))
      (node (ref "SW50") (pin "2") (pinfunction "Out_2") (pintype "output"))
    )
    (net (code "68") (name "Net-(SW51-Out)") (class "Default")
      (node (ref "D51") (pin "1") (pinfunction "1_1") (pintype "passive"))
      (node (ref "SW51") (pin "2") (pinfunction "Out_2") (pintype "output"))
    )
    (net (code "69") (name "Net-(SW52-Out)") (class "Default")
      (node (ref "D52") (pin "1") (pinfunction "1_1") (pintype "passive"))
      (node (ref "SW52") (pin "2") (pinfunction "Out_2") (pintype "output"))
    )
    (net (code "70") (name "Net-(SW53-Out)") (class "Default")
      (node (ref "D53") (pin "1") (pinfunction "1_1") (pintype "passive"))
      (node (ref "SW53") (pin "2") (pinfunction "Out_2") (pintype "output"))
    )
    (net (code "71") (name "Net-(SW54-Out)") (class "Default")
      (node (ref "D54") (pin "1") (pinfunction "1_1") (pintype "passive"))
      (node (ref "SW54") (pin "2") (pinfunction "Out_2") (pintype "output"))
    )
    (net (code "72") (name "Net-(SW55-Out)") (class "Default")
      (node (ref "D55") (pin "1") (pinfunction "1_1") (pintype "passive"))
      (node (ref "SW55") (pin "2") (pinfunction "Out_2") (pintype "output"))
    )
    (net (code "73") (name "Net-(SW56-Out)") (class "Default")
      (node (ref "D56") (pin "1") (pinfunction "1_1") (pintype "passive"))
      (node (ref "SW56") (pin "2") (pinfunction "Out_2") (pintype "output"))
    )
    (net (code "74") (name "Net-(SW57-Out)") (class "Default")
      (node (ref "D57") (pin "1") (pinfunction "1_1") (pintype "passive"))
      (node (ref "SW57") (pin "2") (pinfunction "Out_2") (pintype "output"))
    )
    (net (code "75") (name "Net-(SW58-Out)") (class "Default")
      (node (ref "D58") (pin "1") (pinfunction "1_1") (pintype "passive"))
      (node (ref "SW58") (pin "2") (pinfunction "Out_2") (pintype "output"))
    )
    (net (code "76") (name "Net-(SW59-Out)") (class "Default")
      (node (ref "D59") (pin "1") (pinfunction "1_1") (pintype "passive"))
      (node (ref "SW59") (pin "2") (pinfunction "Out_2") (pintype "output"))
    )
    (net (code "77") (name "Net-(SW60-Out)") (class "Default")
      (node (ref "D60") (pin "1") (pinfunction "1_1") (pintype "passive"))
      (node (ref "SW60") (pin "2") (pinfunction "Out_2") (pintype "output"))
    )
    (net (code "78") (name "Net-(SW61-Out)") (class "Default")
      (node (ref "D61") (pin "1") (pinfunction "1_1") (pintype "passive"))
      (node (ref "SW61") (pin "2") (pinfunction "Out_2") (pintype "output"))
    )
    (net (code "79") (name "Net-(SW62-Out)") (class "Default")
      (node (ref "D62") (pin "1") (pinfunction "1_1") (pintype "passive"))
      (node (ref "SW62") (pin "2") (pinfunction "Out_2") (pintype "output"))
    )
    (net (code "80") (name "Net-(SW63-Out)") (class "Default")
      (node (ref "D63") (pin "1") (pinfunction "1_1") (pintype "passive"))
      (node (ref "SW63") (pin "2") (pinfunction "Out_2") (pintype "output"))
    )
    (net (code "81") (name "Net-(SW64-Out)") (class "Default")
      (node (ref "D64") (pin "1") (pinfunction "1_1") (pintype "passive"))
      (node (ref "SW64") (pin "2") (pinfunction "Out_2") (pintype "output"))
    )
  )
)
